# Sheet1.net
KiCad netlist of a schematic drawn in Altium Designer
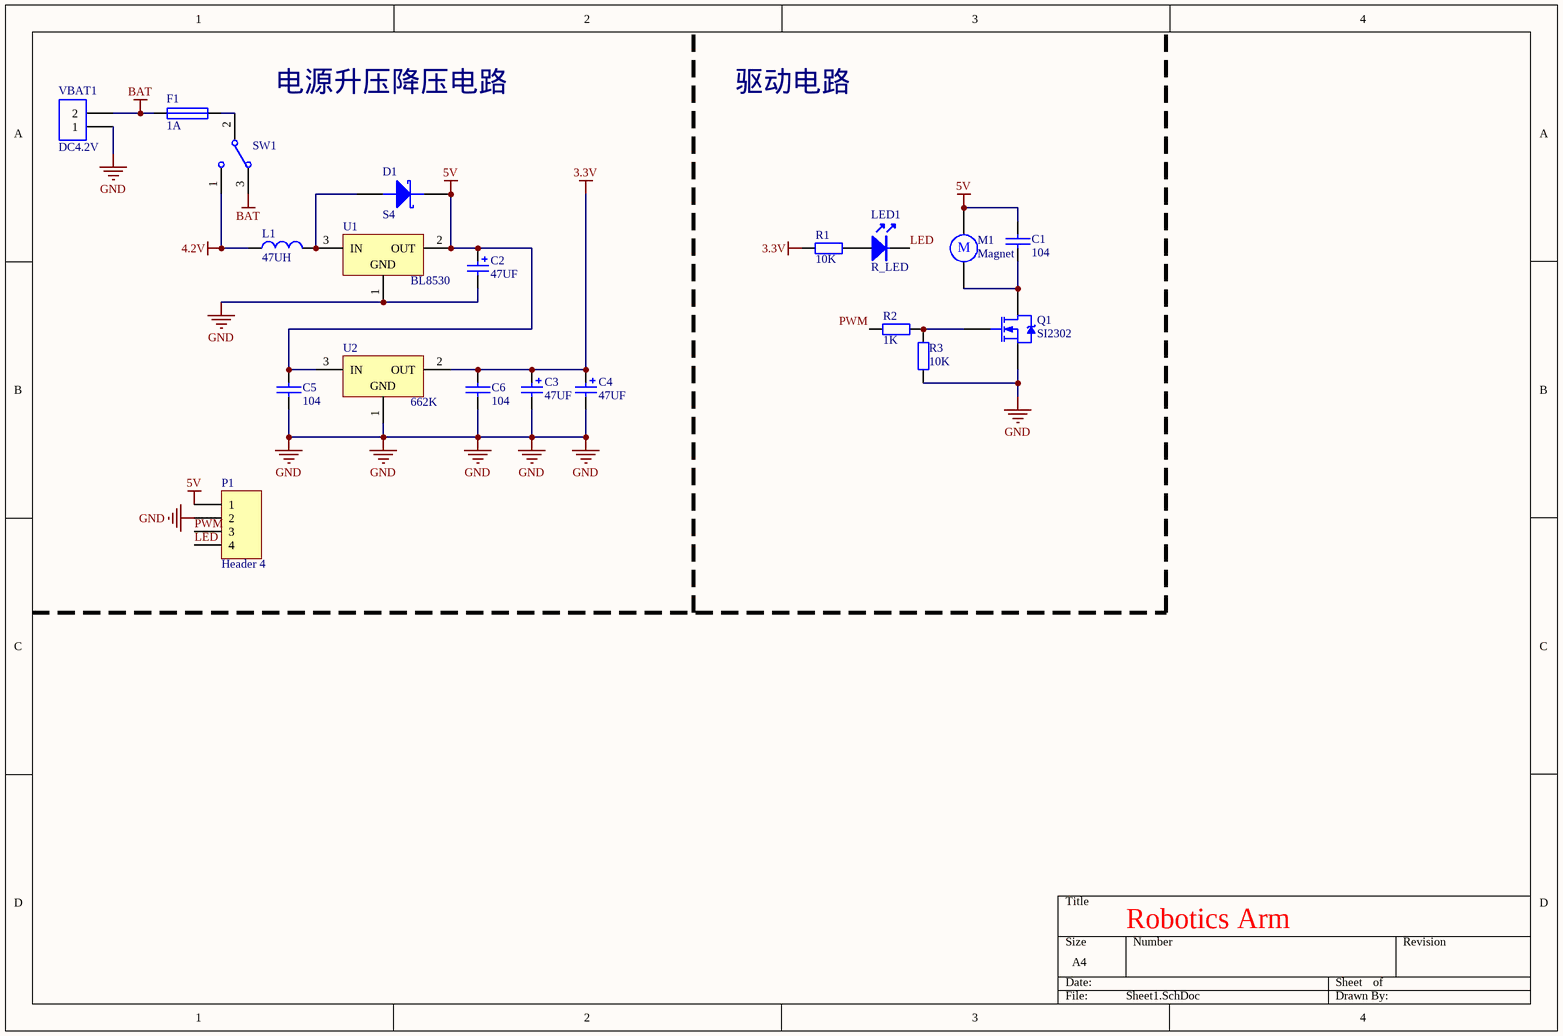
[diagram p0: Sheet1.SchDoc]

(export (version "E")
  (design (tool "Eeschema 10.0.6"))
  (components
    (comp (ref "C1")
      (value "104")
      (footprint "C_0603")
      (description "Capacitor")
      (libsource (lib "原理图封装") (part "CAP"))
    )
    (comp (ref "C2")
      (value "47UF")
      (footprint "1206")
      (description "Polarized Capacitor (Radial)")
      (fields (field (name "PUBLISHER") "Altium Limited"))
      (libsource (lib "原理图封装") (part "Cap Pol1"))
    )
    (comp (ref "C3")
      (value "47UF")
      (footprint "1206")
      (description "Polarized Capacitor (Radial)")
      (fields (field (name "PUBLISHER") "Altium Limited"))
      (libsource (lib "原理图封装") (part "Cap Pol1"))
    )
    (comp (ref "C4")
      (value "47UF")
      (footprint "1206")
      (description "Polarized Capacitor (Radial)")
      (fields (field (name "PUBLISHER") "Altium Limited"))
      (libsource (lib "原理图封装") (part "Cap Pol1"))
    )
    (comp (ref "C5")
      (value "104")
      (footprint "C_0603")
      (description "Capacitor")
      (libsource (lib "原理图封装") (part "CAP"))
    )
    (comp (ref "C6")
      (value "104")
      (footprint "C_0603")
      (description "Capacitor")
      (libsource (lib "原理图封装") (part "CAP"))
    )
    (comp (ref "D1")
      (value "S4")
      (footprint "SOD-123")
      (description "Schottky Diode")
      (libsource (lib "原理图封装") (part "DIODE SCHOTTKY"))
    )
    (comp (ref "F1")
      (value "1A")
      (footprint "C1206")
      (description "Fuse")
      (libsource (lib "原理图封装") (part "FUSE1"))
    )
    (comp (ref "L1")
      (value "47UH")
      (footprint "L_1210")
      (description "Inductor")
      (fields (field (name "Comment") "Inductor Chip") (field (name "PUBLISHER") "Altium Limited"))
      (libsource (lib "原理图封装") (part "Inductor Chip"))
    )
    (comp (ref "LED1") (value "R_LED") (footprint "LED-0603") (libsource (lib "原理图封装") (part "LED")))
    (comp (ref "M1")
      (value "Magnet")
      (footprint "MOTOR")
      (description "Motor, General Kind")
      (fields (field (name "PUBLISHER") "Altium Limited"))
      (libsource (lib "原理图封装") (part "Motor"))
    )
    (comp (ref "P1")
      (value "Header 4")
      (footprint "HDR1X4")
      (description "Header, 4-Pin")
      (fields (field (name "PUBLISHER") "Altium Limited"))
      (libsource (lib "Miscellaneous Connectors") (part "Header 4"))
    )
    (comp (ref "Q1")
      (value "SI2302")
      (footprint "SOT-23(SOT-23-3)")
      (description "N沟道MOSFET")
      (fields (field (name "PUBLISHER") "mazhongwei"))
      (libsource (lib "Sch_Package") (part "SI2302"))
    )
    (comp (ref "R1")
      (value "10K")
      (footprint "R_0603")
      (description "Resistor")
      (fields (field (name "PUBLISHER") "Altium Limited"))
      (libsource (lib "原理图封装") (part "Res2"))
    )
    (comp (ref "R2")
      (value "1K")
      (footprint "R_0603")
      (description "Resistor")
      (fields (field (name "PUBLISHER") "Altium Limited"))
      (libsource (lib "原理图封装") (part "Res2"))
    )
    (comp (ref "R3")
      (value "10K")
      (footprint "R_0603")
      (description "Resistor")
      (fields (field (name "PUBLISHER") "Altium Limited"))
      (libsource (lib "") (part "Res2_1"))
    )
    (comp (ref "SW1")
      (value "SW-SPDT")
      (footprint "SWITCH_PWR")
      (description "SPDT Subminiature Toggle Switch, Right Angle Mounting, Vertical Actuation")
      (fields (field (name "PUBLISHER") "Altium Limited"))
      (libsource (lib "原理图封装") (part "SW-SPDT"))
    )
    (comp (ref "U1")
      (value "BL8530")
      (footprint "SOT-89(SOT-89-3)")
      (libsource (lib "Sch_Package") (part "BL8530"))
    )
    (comp (ref "U2")
      (value "662K")
      (footprint "SOT-23(SOT-23-3)")
      (libsource (lib "Sch_Package") (part "BL8530"))
    )
    (comp (ref "VBAT1")
      (value "DC4.2V")
      (footprint "BAT")
      (description "Connector")
      (libsource (lib "原理图封装") (part "CON2"))
    )
  )
  (nets
    (net (code "1") (name "/LED") (class "Default")
      (node (ref "LED1") (pin "2") (pinfunction "2_2") (pintype "passive"))
      (node (ref "P1") (pin "4") (pinfunction "4_4") (pintype "passive"))
    )
    (net (code "2") (name "/PWM") (class "Default")
      (node (ref "P1") (pin "3") (pinfunction "3_3") (pintype "passive"))
      (node (ref "R2") (pin "1") (pinfunction "1_1") (pintype "passive"))
    )
    (net (code "3") (name "3.3V") (class "Default")
      (node (ref "C3") (pin "1") (pinfunction "1_1") (pintype "passive"))
      (node (ref "C4") (pin "1") (pinfunction "1_1") (pintype "passive"))
      (node (ref "C6") (pin "1") (pinfunction "1_1") (pintype "passive"))
      (node (ref "R1") (pin "1") (pinfunction "1_1") (pintype "passive"))
      (node (ref "U2") (pin "2") (pinfunction "OUT_2") (pintype "power_in"))
    )
    (net (code "4") (name "4.2V") (class "Default")
      (node (ref "L1") (pin "1") (pinfunction "1_1") (pintype "passive"))
      (node (ref "SW1") (pin "1") (pinfunction "1_1") (pintype "passive"))
    )
    (net (code "5") (name "5V") (class "Default")
      (node (ref "C1") (pin "2") (pinfunction "2_2") (pintype "passive"))
      (node (ref "C2") (pin "1") (pinfunction "1_1") (pintype "passive"))
      (node (ref "C5") (pin "1") (pinfunction "1_1") (pintype "passive"))
      (node (ref "D1") (pin "2") (pinfunction "K_2") (pintype "passive"))
      (node (ref "M1") (pin "1") (pinfunction "1_1") (pintype "passive"))
      (node (ref "P1") (pin "1") (pinfunction "1_1") (pintype "passive"))
      (node (ref "U1") (pin "2") (pinfunction "OUT_2") (pintype "power_in"))
      (node (ref "U2") (pin "3") (pinfunction "IN_3") (pintype "power_in"))
    )
    (net (code "6") (name "BAT") (class "Default")
      (node (ref "F1") (pin "2") (pinfunction "2_2") (pintype "passive"))
      (node (ref "SW1") (pin "3") (pinfunction "3_3") (pintype "passive"))
      (node (ref "VBAT1") (pin "2") (pinfunction "2_2") (pintype "passive"))
    )
    (net (code "7") (name "GND") (class "Default")
      (node (ref "C2") (pin "2") (pinfunction "2_2") (pintype "passive"))
      (node (ref "C3") (pin "2") (pinfunction "2_2") (pintype "passive"))
      (node (ref "C4") (pin "2") (pinfunction "2_2") (pintype "passive"))
      (node (ref "C5") (pin "2") (pinfunction "2_2") (pintype "passive"))
      (node (ref "C6") (pin "2") (pinfunction "2_2") (pintype "passive"))
      (node (ref "P1") (pin "2") (pinfunction "2_2") (pintype "passive"))
      (node (ref "Q1") (pin "2") (pinfunction "S_2") (pintype "passive"))
      (node (ref "R3") (pin "1") (pinfunction "1_1") (pintype "passive"))
      (node (ref "U1") (pin "1") (pinfunction "GND_1") (pintype "power_in"))
      (node (ref "U2") (pin "1") (pinfunction "GND_1") (pintype "power_in"))
      (node (ref "VBAT1") (pin "1") (pinfunction "1_1") (pintype "passive"))
    )
    (net (code "8") (name "Net-(D1-A)") (class "Default")
      (node (ref "D1") (pin "1") (pinfunction "A_1") (pintype "passive"))
      (node (ref "L1") (pin "2") (pinfunction "2_2") (pintype "passive"))
      (node (ref "U1") (pin "3") (pinfunction "IN_3") (pintype "power_in"))
    )
    (net (code "9") (name "Net-(F1-Pad1)") (class "Default")
      (node (ref "F1") (pin "1") (pinfunction "1_1") (pintype "passive"))
      (node (ref "SW1") (pin "2") (pinfunction "2_2") (pintype "passive"))
    )
    (net (code "10") (name "Net-(LED1-Pad1)") (class "Default")
      (node (ref "LED1") (pin "1") (pinfunction "1_1") (pintype "passive"))
      (node (ref "R1") (pin "2") (pinfunction "2_2") (pintype "passive"))
    )
    (net (code "11") (name "Net-(Q1-D)") (class "Default")
      (node (ref "C1") (pin "1") (pinfunction "1_1") (pintype "passive"))
      (node (ref "M1") (pin "2") (pinfunction "2_2") (pintype "passive"))
      (node (ref "Q1") (pin "3") (pinfunction "D_3") (pintype "passive"))
    )
    (net (code "12") (name "Net-(Q1-G)") (class "Default")
      (node (ref "Q1") (pin "1") (pinfunction "G_1") (pintype "passive"))
      (node (ref "R2") (pin "2") (pinfunction "2_2") (pintype "passive"))
      (node (ref "R3") (pin "2") (pinfunction "2_2") (pintype "passive"))
    )
  )
)
